# design.net
KiCad netlist of a schematic drawn in Altium Designer
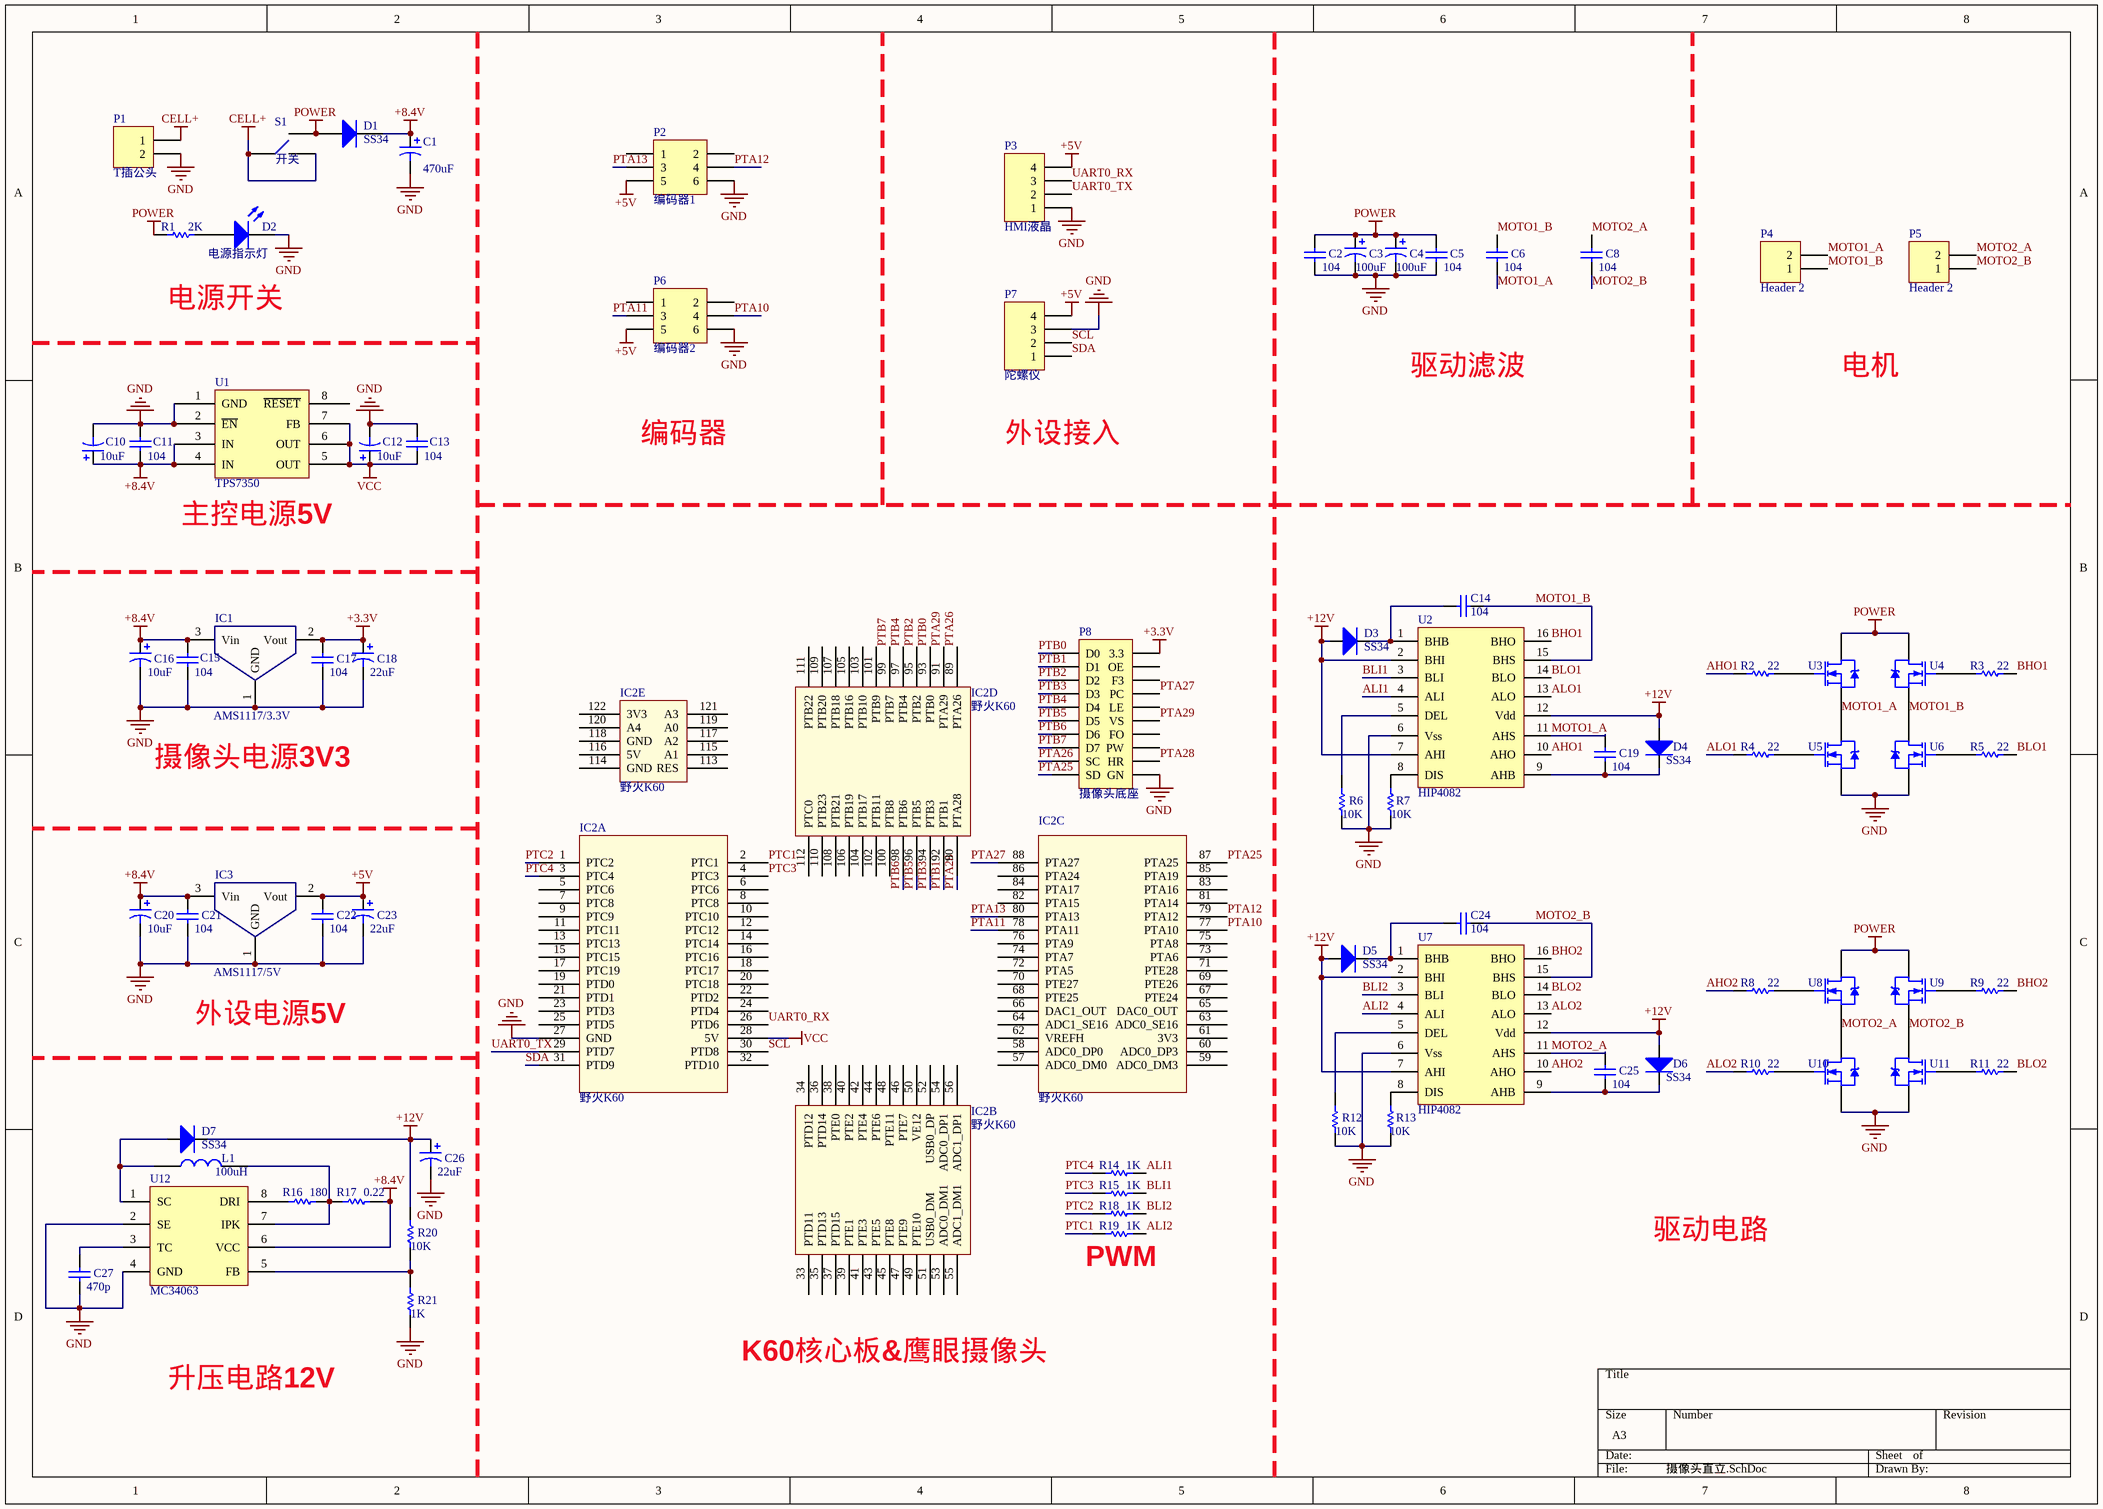
[diagram p0: 摄像头直立.SchDoc]

(export (version "E")
  (design (tool "Eeschema 10.0.6"))
  (components
    (comp (ref "C1")
      (value "470uF")
      (footprint "CAP_ELEC_250P680X1220_FLAT2")
      (description "Polarized Capacitor (Radial)")
      (fields (field (name "Comment") "Cap Pol1") (field (name "PUBLISHER") "Altium Limited"))
      (libsource (lib "Miscellaneous Devices") (part "Cap Pol1"))
    )
    (comp (ref "C2")
      (value "104")
      (footprint "CAP_0805")
      (description "Capacitor")
      (fields (field (name "Comment") "Cap") (field (name "PUBLISHER") "Altium Limited"))
      (libsource (lib "Miscellaneous Devices") (part "Cap"))
    )
    (comp (ref "C3")
      (value "100uF")
      (footprint "CAP_ELEC_250P680X1220_VERT")
      (description "Polarized Capacitor (Radial)")
      (fields (field (name "PUBLISHER") "Altium Limited"))
      (libsource (lib "Miscellaneous Devices") (part "Cap Pol1"))
    )
    (comp (ref "C4")
      (value "100uF")
      (footprint "CAP_ELEC_250P680X1220_VERT")
      (description "Polarized Capacitor (Radial)")
      (fields (field (name "PUBLISHER") "Altium Limited"))
      (libsource (lib "Miscellaneous Devices") (part "Cap Pol1"))
    )
    (comp (ref "C5")
      (value "104")
      (footprint "CAP_0805")
      (description "Capacitor")
      (fields (field (name "Comment") "Cap") (field (name "PUBLISHER") "Altium Limited"))
      (libsource (lib "Miscellaneous Devices") (part "Cap"))
    )
    (comp (ref "C6")
      (value "104")
      (footprint "CAP_0805")
      (description "Capacitor")
      (fields (field (name "Comment") "Cap") (field (name "PUBLISHER") "Altium Limited"))
      (libsource (lib "Miscellaneous Devices") (part "Cap"))
    )
    (comp (ref "C8")
      (value "104")
      (footprint "CAP_0805")
      (description "Capacitor")
      (fields (field (name "Comment") "Cap") (field (name "PUBLISHER") "Altium Limited"))
      (libsource (lib "Miscellaneous Devices") (part "Cap"))
    )
    (comp (ref "C10")
      (value "10uF")
      (footprint "CAP_0805")
      (description "Polarized Capacitor (Radial)")
      (fields (field (name "Comment") "Cap") (field (name "PUBLISHER") "Altium Limited"))
      (libsource (lib "Miscellaneous Devices") (part "Cap Pol1"))
    )
    (comp (ref "C11")
      (value "104")
      (footprint "CAP_0805")
      (description "Capacitor")
      (fields (field (name "Comment") "Cap") (field (name "PUBLISHER") "Altium Limited"))
      (libsource (lib "Miscellaneous Devices") (part "Cap"))
    )
    (comp (ref "C12")
      (value "10uF")
      (footprint "CAP_0805")
      (description "Polarized Capacitor (Radial)")
      (fields (field (name "Comment") "Cap") (field (name "PUBLISHER") "Altium Limited"))
      (libsource (lib "Miscellaneous Devices") (part "Cap Pol1"))
    )
    (comp (ref "C13")
      (value "104")
      (footprint "CAP_0805")
      (description "Capacitor")
      (fields (field (name "Comment") "Cap") (field (name "PUBLISHER") "Altium Limited"))
      (libsource (lib "Miscellaneous Devices") (part "Cap"))
    )
    (comp (ref "C14")
      (value "104")
      (footprint "CAP_0805")
      (description "Capacitor")
      (fields (field (name "Comment") "Cap") (field (name "PUBLISHER") "Altium Limited"))
      (libsource (lib "Miscellaneous Devices") (part "Cap"))
    )
    (comp (ref "C15")
      (value "104")
      (footprint "CAP_0805")
      (description "Capacitor")
      (fields (field (name "Comment") "Cap") (field (name "PUBLISHER") "Altium Limited"))
      (libsource (lib "Miscellaneous Devices") (part "Cap"))
    )
    (comp (ref "C16")
      (value "10uF")
      (footprint "CAP_0805")
      (description "Polarized Capacitor (Radial)")
      (fields (field (name "Comment") "Cap Pol1") (field (name "PUBLISHER") "Altium Limited"))
      (libsource (lib "Miscellaneous Devices") (part "Cap Pol1"))
    )
    (comp (ref "C17")
      (value "104")
      (footprint "CAP_0805")
      (description "Capacitor")
      (fields (field (name "Comment") "Cap") (field (name "PUBLISHER") "Altium Limited"))
      (libsource (lib "Miscellaneous Devices") (part "Cap"))
    )
    (comp (ref "C18")
      (value "22uF")
      (footprint "CAP_0805")
      (description "Polarized Capacitor (Radial)")
      (fields (field (name "Comment") "Cap Pol1") (field (name "PUBLISHER") "Altium Limited"))
      (libsource (lib "Miscellaneous Devices") (part "Cap Pol1"))
    )
    (comp (ref "C19")
      (value "104")
      (footprint "CAP_0805")
      (description "Capacitor")
      (fields (field (name "PUBLISHER") "Altium Limited"))
      (libsource (lib "Miscellaneous Devices") (part "Cap"))
    )
    (comp (ref "C20")
      (value "10uF")
      (footprint "CAP_0805")
      (description "Polarized Capacitor (Radial)")
      (fields (field (name "Comment") "Cap Pol1") (field (name "PUBLISHER") "Altium Limited"))
      (libsource (lib "Miscellaneous Devices") (part "Cap Pol1"))
    )
    (comp (ref "C21")
      (value "104")
      (footprint "CAP_0805")
      (description "Capacitor")
      (fields (field (name "Comment") "Cap") (field (name "PUBLISHER") "Altium Limited"))
      (libsource (lib "Miscellaneous Devices") (part "Cap"))
    )
    (comp (ref "C22")
      (value "104")
      (footprint "CAP_0805")
      (description "Capacitor")
      (fields (field (name "Comment") "Cap") (field (name "PUBLISHER") "Altium Limited"))
      (libsource (lib "Miscellaneous Devices") (part "Cap"))
    )
    (comp (ref "C23")
      (value "22uF")
      (footprint "CAP_0805")
      (description "Polarized Capacitor (Radial)")
      (fields (field (name "Comment") "Cap Pol1") (field (name "PUBLISHER") "Altium Limited"))
      (libsource (lib "Miscellaneous Devices") (part "Cap Pol1"))
    )
    (comp (ref "C24")
      (value "104")
      (footprint "CAP_0805")
      (description "Capacitor")
      (fields (field (name "Comment") "Cap") (field (name "PUBLISHER") "Altium Limited"))
      (libsource (lib "Miscellaneous Devices") (part "Cap"))
    )
    (comp (ref "C25")
      (value "104")
      (footprint "CAP_0805")
      (description "Capacitor")
      (fields (field (name "PUBLISHER") "Altium Limited"))
      (libsource (lib "Miscellaneous Devices") (part "Cap"))
    )
    (comp (ref "C26")
      (value "22uF")
      (footprint "CAP_0805")
      (description "Polarized Capacitor (Radial)")
      (fields (field (name "Comment") "Cap Pol1") (field (name "PUBLISHER") "Altium Limited"))
      (libsource (lib "Miscellaneous Devices") (part "Cap Pol1"))
    )
    (comp (ref "C27")
      (value "470p")
      (footprint "CAP_0805")
      (description "Capacitor")
      (fields (field (name "Comment") "Cap") (field (name "PUBLISHER") "Altium Limited"))
      (libsource (lib "Miscellaneous Devices") (part "Cap"))
    )
    (comp (ref "D1")
      (value "SS34")
      (footprint "SMA")
      (description "Default Diode")
      (fields (field (name "PUBLISHER") "Altium Limited"))
      (libsource (lib "Miscellaneous Devices") (part "Diode"))
    )
    (comp (ref "D2")
      (value "电源指示灯")
      (footprint "DIO_0805")
      (description "Typical INFRARED GaAs LED")
      (fields (field (name "PUBLISHER") "Altium Limited"))
      (libsource (lib "Miscellaneous Devices") (part "LED0"))
    )
    (comp (ref "D3") (value "SS34") (footprint "SMA") (libsource (lib "lr7843_new") (part "1n4007_2010")))
    (comp (ref "D4") (value "SS34") (footprint "SMA") (libsource (lib "lr7843_new") (part "1n4007_2010")))
    (comp (ref "D5") (value "SS34") (footprint "SMA") (libsource (lib "lr7843_new") (part "1n4007_2010")))
    (comp (ref "D6") (value "SS34") (footprint "SMA") (libsource (lib "lr7843_new") (part "1n4007_2010")))
    (comp (ref "D7") (value "SS34") (footprint "SMA") (libsource (lib "lr7843_new") (part "1n4007_2010")))
    (comp (ref "IC1")
      (value "AMS1117/3.3V")
      (footprint "SOT_223")
      (libsource (lib "Power_IC") (part "AMS1117"))
    )
    (comp (ref "IC2") (value "野火K60") (footprint "fireK60") (libsource (lib "Mcu_IC") (part "野火K60")))
    (comp (ref "IC3")
      (value "AMS1117/5V")
      (footprint "SOT_223")
      (libsource (lib "Power_IC") (part "AMS1117"))
    )
    (comp (ref "L1")
      (value "100uH")
      (footprint "L-5X4mm-S")
      (fields (field (name "Comment") "inductor"))
      (libsource (lib "lr7843_new") (part "inductor_CD43贴片"))
    )
    (comp (ref "P1")
      (value "T插公头")
      (footprint "T(G)")
      (description "Header, 2-Pin")
      (fields (field (name "PUBLISHER") "Altium Limited"))
      (libsource (lib "") (part "Header 2_1"))
    )
    (comp (ref "P2")
      (value "编码器1")
      (footprint "201R2X3")
      (description "Header, 3-Pin, Dual row")
      (fields (field (name "PUBLISHER") "Altium Limited"))
      (libsource (lib "Miscellaneous Connectors") (part "Header 3X2"))
    )
    (comp (ref "P3")
      (value "HMI液晶")
      (footprint "HDR1*4")
      (description "Header, 4-Pin")
      (fields (field (name "PUBLISHER") "Altium Limited"))
      (libsource (lib "Miscellaneous Connectors") (part "Header 4"))
    )
    (comp (ref "P4")
      (value "Header 2")
      (footprint "CON_5.08*2")
      (description "Header, 2-Pin")
      (fields (field (name "PUBLISHER") "Altium Limited"))
      (libsource (lib "Miscellaneous Connectors") (part "Header 2"))
    )
    (comp (ref "P5")
      (value "Header 2")
      (footprint "CON_5.08*2")
      (description "Header, 2-Pin")
      (fields (field (name "PUBLISHER") "Altium Limited"))
      (libsource (lib "Miscellaneous Connectors") (part "Header 2"))
    )
    (comp (ref "P6")
      (value "编码器2")
      (footprint "201R2X3")
      (description "Header, 3-Pin, Dual row")
      (fields (field (name "PUBLISHER") "Altium Limited"))
      (libsource (lib "Miscellaneous Connectors") (part "Header 3X2"))
    )
    (comp (ref "P7")
      (value "陀螺仪")
      (footprint "HDR1*4")
      (description "Header, 4-Pin")
      (fields (field (name "PUBLISHER") "Altium Limited"))
      (libsource (lib "Miscellaneous Connectors") (part "Header 4"))
    )
    (comp (ref "P8")
      (value "摄像头底座")
      (footprint "摄像头")
      (description "Header, 10-Pin, Dual row, Right Angle")
      (fields (field (name "PUBLISHER") "Altium Limited"))
      (libsource (lib "Miscellaneous Connectors") (part "Header 10X2H"))
    )
    (comp (ref "R1")
      (value "2K")
      (footprint "RES_0805")
      (description "Resistor")
      (fields (field (name "Comment") "Res1") (field (name "PUBLISHER") "Altium Limited"))
      (libsource (lib "Miscellaneous Devices") (part "Res1"))
    )
    (comp (ref "R2")
      (value "22")
      (footprint "RES_0805")
      (description "Resistor")
      (fields (field (name "Comment") "Res1") (field (name "PUBLISHER") "Altium Limited"))
      (libsource (lib "Miscellaneous Devices") (part "Res1"))
    )
    (comp (ref "R3")
      (value "22")
      (footprint "RES_0805")
      (description "Resistor")
      (fields (field (name "Comment") "Res1") (field (name "PUBLISHER") "Altium Limited"))
      (libsource (lib "Miscellaneous Devices") (part "Res1"))
    )
    (comp (ref "R4")
      (value "22")
      (footprint "RES_0805")
      (description "Resistor")
      (fields (field (name "Comment") "Res1") (field (name "PUBLISHER") "Altium Limited"))
      (libsource (lib "Miscellaneous Devices") (part "Res1"))
    )
    (comp (ref "R5")
      (value "22")
      (footprint "RES_0805")
      (description "Resistor")
      (fields (field (name "Comment") "Res1") (field (name "PUBLISHER") "Altium Limited"))
      (libsource (lib "Miscellaneous Devices") (part "Res1"))
    )
    (comp (ref "R6")
      (value "10K")
      (footprint "RES_0805")
      (description "Resistor")
      (fields (field (name "Comment") "Res1") (field (name "PUBLISHER") "Altium Limited"))
      (libsource (lib "Miscellaneous Devices") (part "Res1"))
    )
    (comp (ref "R7")
      (value "10K")
      (footprint "RES_0805")
      (description "Resistor")
      (fields (field (name "Comment") "Res1") (field (name "PUBLISHER") "Altium Limited"))
      (libsource (lib "Miscellaneous Devices") (part "Res1"))
    )
    (comp (ref "R8")
      (value "22")
      (footprint "RES_0805")
      (description "Resistor")
      (fields (field (name "Comment") "Res1") (field (name "PUBLISHER") "Altium Limited"))
      (libsource (lib "Miscellaneous Devices") (part "Res1"))
    )
    (comp (ref "R9")
      (value "22")
      (footprint "RES_0805")
      (description "Resistor")
      (fields (field (name "Comment") "Res1") (field (name "PUBLISHER") "Altium Limited"))
      (libsource (lib "Miscellaneous Devices") (part "Res1"))
    )
    (comp (ref "R10")
      (value "22")
      (footprint "RES_0805")
      (description "Resistor")
      (fields (field (name "Comment") "Res1") (field (name "PUBLISHER") "Altium Limited"))
      (libsource (lib "Miscellaneous Devices") (part "Res1"))
    )
    (comp (ref "R11")
      (value "22")
      (footprint "RES_0805")
      (description "Resistor")
      (fields (field (name "Comment") "Res1") (field (name "PUBLISHER") "Altium Limited"))
      (libsource (lib "Miscellaneous Devices") (part "Res1"))
    )
    (comp (ref "R12")
      (value "10K")
      (footprint "RES_0805")
      (description "Resistor")
      (fields (field (name "Comment") "Res1") (field (name "PUBLISHER") "Altium Limited"))
      (libsource (lib "Miscellaneous Devices") (part "Res1"))
    )
    (comp (ref "R13")
      (value "10K")
      (footprint "RES_0805")
      (description "Resistor")
      (fields (field (name "Comment") "Res1") (field (name "PUBLISHER") "Altium Limited"))
      (libsource (lib "Miscellaneous Devices") (part "Res1"))
    )
    (comp (ref "R14")
      (value "1K")
      (footprint "RES_0805")
      (description "Resistor")
      (fields (field (name "PUBLISHER") "Altium Limited"))
      (libsource (lib "Miscellaneous Devices") (part "Res1"))
    )
    (comp (ref "R15")
      (value "1K")
      (footprint "RES_0805")
      (description "Resistor")
      (fields (field (name "PUBLISHER") "Altium Limited"))
      (libsource (lib "Miscellaneous Devices") (part "Res1"))
    )
    (comp (ref "R16")
      (value "180")
      (footprint "RES_0805")
      (description "Resistor")
      (fields (field (name "PUBLISHER") "Altium Limited"))
      (libsource (lib "Miscellaneous Devices") (part "Res1"))
    )
    (comp (ref "R17")
      (value "0.22")
      (footprint "RES_1206")
      (description "Resistor")
      (fields (field (name "PUBLISHER") "Altium Limited"))
      (libsource (lib "Miscellaneous Devices") (part "Res1"))
    )
    (comp (ref "R18")
      (value "1K")
      (footprint "RES_0805")
      (description "Resistor")
      (fields (field (name "PUBLISHER") "Altium Limited"))
      (libsource (lib "Miscellaneous Devices") (part "Res1"))
    )
    (comp (ref "R19")
      (value "1K")
      (footprint "RES_0805")
      (description "Resistor")
      (fields (field (name "PUBLISHER") "Altium Limited"))
      (libsource (lib "Miscellaneous Devices") (part "Res1"))
    )
    (comp (ref "R20")
      (value "10K")
      (footprint "RES_0805")
      (description "Resistor")
      (fields (field (name "PUBLISHER") "Altium Limited"))
      (libsource (lib "Miscellaneous Devices") (part "Res1"))
    )
    (comp (ref "R21")
      (value "1K")
      (footprint "RES_0805")
      (description "Resistor")
      (fields (field (name "PUBLISHER") "Altium Limited"))
      (libsource (lib "Miscellaneous Devices") (part "Res1"))
    )
    (comp (ref "S1")
      (value "开关")
      (footprint "slide_switch")
      (libsource (lib "lr7843_new") (part "slide_switch"))
    )
    (comp (ref "U1") (value "TPS7350") (footprint "SOP_8") (libsource (lib "Power_IC") (part "TPS73XX")))
    (comp (ref "U2") (value "HIP4082") (footprint "HIP4082b") (libsource (lib "lr7843_new") (part "HIP4082")))
    (comp (ref "U3")
      (value "irlr7843")
      (footprint "TO-252AA")
      (libsource (lib "lr7843_new") (part "IRLR7843"))
    )
    (comp (ref "U4")
      (value "irlr7843")
      (footprint "TO-252AA")
      (libsource (lib "lr7843_new") (part "IRLR7843"))
    )
    (comp (ref "U5")
      (value "irlr7843")
      (footprint "TO-252AA")
      (libsource (lib "lr7843_new") (part "IRLR7843"))
    )
    (comp (ref "U6")
      (value "irlr7843")
      (footprint "TO-252AA")
      (libsource (lib "lr7843_new") (part "IRLR7843"))
    )
    (comp (ref "U7") (value "HIP4082") (footprint "HIP4082b") (libsource (lib "lr7843_new") (part "HIP4082")))
    (comp (ref "U8")
      (value "irlr7843")
      (footprint "TO-252AA")
      (libsource (lib "lr7843_new") (part "IRLR7843"))
    )
    (comp (ref "U9")
      (value "irlr7843")
      (footprint "TO-252AA")
      (libsource (lib "lr7843_new") (part "IRLR7843"))
    )
    (comp (ref "U10")
      (value "irlr7843")
      (footprint "TO-252AA")
      (libsource (lib "lr7843_new") (part "IRLR7843"))
    )
    (comp (ref "U11")
      (value "irlr7843")
      (footprint "TO-252AA")
      (libsource (lib "lr7843_new") (part "IRLR7843"))
    )
    (comp (ref "U12") (value "MC34063") (footprint "SOP_8") (libsource (lib "lr7843_new") (part "MC34063")))
  )
  (nets
    (net (code "1") (name "+3.3V") (class "Default")
      (node (ref "C17") (pin "2") (pinfunction "2_2") (pintype "passive"))
      (node (ref "C18") (pin "1") (pinfunction "1_1") (pintype "passive"))
      (node (ref "IC1") (pin "2") (pinfunction "Vout_2") (pintype "passive"))
      (node (ref "P8") (pin "2") (pinfunction "3.3_2") (pintype "passive"))
    )
    (net (code "2") (name "+5V") (class "Default")
      (node (ref "C22") (pin "2") (pinfunction "2_2") (pintype "passive"))
      (node (ref "C23") (pin "1") (pinfunction "1_1") (pintype "passive"))
      (node (ref "IC3") (pin "2") (pinfunction "Vout_2") (pintype "passive"))
      (node (ref "P2") (pin "5") (pinfunction "5_5") (pintype "passive"))
      (node (ref "P3") (pin "4") (pinfunction "4_4") (pintype "passive"))
      (node (ref "P6") (pin "5") (pinfunction "5_5") (pintype "passive"))
      (node (ref "P7") (pin "4") (pinfunction "4_4") (pintype "passive"))
    )
    (net (code "3") (name "+8.4V") (class "Default")
      (node (ref "C1") (pin "1") (pinfunction "1_1") (pintype "passive"))
      (node (ref "C10") (pin "1") (pinfunction "1_1") (pintype "passive"))
      (node (ref "C11") (pin "1") (pinfunction "1_1") (pintype "passive"))
      (node (ref "C15") (pin "2") (pinfunction "2_2") (pintype "passive"))
      (node (ref "C16") (pin "1") (pinfunction "1_1") (pintype "passive"))
      (node (ref "C20") (pin "1") (pinfunction "1_1") (pintype "passive"))
      (node (ref "C21") (pin "2") (pinfunction "2_2") (pintype "passive"))
      (node (ref "D1") (pin "2") (pinfunction "K_2") (pintype "passive"))
      (node (ref "IC1") (pin "3") (pinfunction "Vin_3") (pintype "passive"))
      (node (ref "IC3") (pin "3") (pinfunction "Vin_3") (pintype "passive"))
      (node (ref "R17") (pin "1") (pinfunction "1_1") (pintype "passive"))
      (node (ref "U1") (pin "3") (pinfunction "IN_3") (pintype "passive"))
      (node (ref "U1") (pin "4") (pinfunction "IN_4") (pintype "passive"))
      (node (ref "U12") (pin "6") (pinfunction "VCC_6") (pintype "passive"))
    )
    (net (code "4") (name "+12V") (class "Default")
      (node (ref "C26") (pin "1") (pinfunction "1_1") (pintype "passive"))
      (node (ref "D3") (pin "1") (pinfunction "A_1") (pintype "passive"))
      (node (ref "D4") (pin "1") (pinfunction "A_1") (pintype "passive"))
      (node (ref "D5") (pin "1") (pinfunction "A_1") (pintype "passive"))
      (node (ref "D6") (pin "1") (pinfunction "A_1") (pintype "passive"))
      (node (ref "D7") (pin "2") (pinfunction "K_2") (pintype "passive"))
      (node (ref "R20") (pin "2") (pinfunction "2_2") (pintype "passive"))
      (node (ref "U2") (pin "12") (pinfunction "Vdd_12") (pintype "passive"))
      (node (ref "U2") (pin "2") (pinfunction "BHI_2") (pintype "passive"))
      (node (ref "U2") (pin "7") (pinfunction "AHI_7") (pintype "passive"))
      (node (ref "U7") (pin "12") (pinfunction "Vdd_12") (pintype "passive"))
      (node (ref "U7") (pin "2") (pinfunction "BHI_2") (pintype "passive"))
      (node (ref "U7") (pin "7") (pinfunction "AHI_7") (pintype "passive"))
    )
    (net (code "5") (name "/AHO1") (class "Default")
      (node (ref "R2") (pin "2") (pinfunction "2_2") (pintype "passive"))
      (node (ref "U2") (pin "10") (pinfunction "AHO_10") (pintype "passive"))
    )
    (net (code "6") (name "/AHO2") (class "Default")
      (node (ref "R8") (pin "2") (pinfunction "2_2") (pintype "passive"))
      (node (ref "U7") (pin "10") (pinfunction "AHO_10") (pintype "passive"))
    )
    (net (code "7") (name "/ALI1") (class "Default")
      (node (ref "R14") (pin "1") (pinfunction "1_1") (pintype "passive"))
      (node (ref "U2") (pin "4") (pinfunction "ALI_4") (pintype "passive"))
    )
    (net (code "8") (name "/ALI2") (class "Default")
      (node (ref "R19") (pin "1") (pinfunction "1_1") (pintype "passive"))
      (node (ref "U7") (pin "4") (pinfunction "ALI_4") (pintype "passive"))
    )
    (net (code "9") (name "/ALO1") (class "Default")
      (node (ref "R4") (pin "2") (pinfunction "2_2") (pintype "passive"))
      (node (ref "U2") (pin "13") (pinfunction "ALO_13") (pintype "passive"))
    )
    (net (code "10") (name "/ALO2") (class "Default")
      (node (ref "R10") (pin "2") (pinfunction "2_2") (pintype "passive"))
      (node (ref "U7") (pin "13") (pinfunction "ALO_13") (pintype "passive"))
    )
    (net (code "11") (name "/BHO1") (class "Default")
      (node (ref "R3") (pin "1") (pinfunction "1_1") (pintype "passive"))
      (node (ref "U2") (pin "16") (pinfunction "BHO_16") (pintype "passive"))
    )
    (net (code "12") (name "/BHO2") (class "Default")
      (node (ref "R9") (pin "1") (pinfunction "1_1") (pintype "passive"))
      (node (ref "U7") (pin "16") (pinfunction "BHO_16") (pintype "passive"))
    )
    (net (code "13") (name "/BLI1") (class "Default")
      (node (ref "R15") (pin "1") (pinfunction "1_1") (pintype "passive"))
      (node (ref "U2") (pin "3") (pinfunction "BLI_3") (pintype "passive"))
    )
    (net (code "14") (name "/BLI2") (class "Default")
      (node (ref "R18") (pin "1") (pinfunction "1_1") (pintype "passive"))
      (node (ref "U7") (pin "3") (pinfunction "BLI_3") (pintype "passive"))
    )
    (net (code "15") (name "/BLO1") (class "Default")
      (node (ref "R5") (pin "1") (pinfunction "1_1") (pintype "passive"))
      (node (ref "U2") (pin "14") (pinfunction "BLO_14") (pintype "passive"))
    )
    (net (code "16") (name "/BLO2") (class "Default")
      (node (ref "R11") (pin "1") (pinfunction "1_1") (pintype "passive"))
      (node (ref "U7") (pin "14") (pinfunction "BLO_14") (pintype "passive"))
    )
    (net (code "17") (name "/MOTO1_A") (class "Default")
      (node (ref "C19") (pin "2") (pinfunction "2_2") (pintype "passive"))
      (node (ref "C6") (pin "2") (pinfunction "2_2") (pintype "passive"))
      (node (ref "P4") (pin "2") (pinfunction "2_2") (pintype "passive"))
      (node (ref "U2") (pin "11") (pinfunction "AHS_11") (pintype "passive"))
      (node (ref "U3") (pin "S") (pinfunction "S_S") (pintype "passive"))
      (node (ref "U5") (pin "D") (pinfunction "D_D") (pintype "passive"))
    )
    (net (code "18") (name "/MOTO1_B") (class "Default")
      (node (ref "C14") (pin "1") (pinfunction "1_1") (pintype "passive"))
      (node (ref "C6") (pin "1") (pinfunction "1_1") (pintype "passive"))
      (node (ref "P4") (pin "1") (pinfunction "1_1") (pintype "passive"))
      (node (ref "U2") (pin "15") (pinfunction "BHS_15") (pintype "passive"))
      (node (ref "U4") (pin "S") (pinfunction "S_S") (pintype "passive"))
      (node (ref "U6") (pin "D") (pinfunction "D_D") (pintype "passive"))
    )
    (net (code "19") (name "/MOTO2_A") (class "Default")
      (node (ref "C25") (pin "2") (pinfunction "2_2") (pintype "passive"))
      (node (ref "C8") (pin "1") (pinfunction "1_1") (pintype "passive"))
      (node (ref "P5") (pin "2") (pinfunction "2_2") (pintype "passive"))
      (node (ref "U10") (pin "D") (pinfunction "D_D") (pintype "passive"))
      (node (ref "U7") (pin "11") (pinfunction "AHS_11") (pintype "passive"))
      (node (ref "U8") (pin "S") (pinfunction "S_S") (pintype "passive"))
    )
    (net (code "20") (name "/MOTO2_B") (class "Default")
      (node (ref "C24") (pin "1") (pinfunction "1_1") (pintype "passive"))
      (node (ref "C8") (pin "2") (pinfunction "2_2") (pintype "passive"))
      (node (ref "P5") (pin "1") (pinfunction "1_1") (pintype "passive"))
      (node (ref "U11") (pin "D") (pinfunction "D_D") (pintype "passive"))
      (node (ref "U7") (pin "15") (pinfunction "BHS_15") (pintype "passive"))
      (node (ref "U9") (pin "S") (pinfunction "S_S") (pintype "passive"))
    )
    (net (code "21") (name "/PTA10") (class "Default")
      (node (ref "IC2") (pin "77") (pinfunction "PTA10_77") (pintype "passive"))
      (node (ref "P6") (pin "4") (pinfunction "4_4") (pintype "passive"))
    )
    (net (code "22") (name "/PTA11") (class "Default")
      (node (ref "IC2") (pin "78") (pinfunction "PTA11_78") (pintype "passive"))
      (node (ref "P6") (pin "3") (pinfunction "3_3") (pintype "passive"))
    )
    (net (code "23") (name "/PTA12") (class "Default")
      (node (ref "IC2") (pin "79") (pinfunction "PTA12_79") (pintype "passive"))
      (node (ref "P2") (pin "4") (pinfunction "4_4") (pintype "passive"))
    )
    (net (code "24") (name "/PTA13") (class "Default")
      (node (ref "IC2") (pin "80") (pinfunction "PTA13_80") (pintype "passive"))
      (node (ref "P2") (pin "3") (pinfunction "3_3") (pintype "passive"))
    )
    (net (code "25") (name "/PTA25") (class "Default")
      (node (ref "IC2") (pin "87") (pinfunction "PTA25_87") (pintype "passive"))
      (node (ref "P8") (pin "19") (pinfunction "SD_19") (pintype "passive"))
    )
    (net (code "26") (name "/PTA26") (class "Default")
      (node (ref "IC2") (pin "89") (pinfunction "PTA26_89") (pintype "passive"))
      (node (ref "P8") (pin "17") (pinfunction "SC_17") (pintype "passive"))
    )
    (net (code "27") (name "/PTA27") (class "Default")
      (node (ref "IC2") (pin "88") (pinfunction "PTA27_88") (pintype "passive"))
      (node (ref "P8") (pin "8") (pinfunction "PC_8") (pintype "passive"))
    )
    (net (code "28") (name "/PTA28") (class "Default")
      (node (ref "IC2") (pin "90") (pinfunction "PTA28_90") (pintype "passive"))
      (node (ref "P8") (pin "18") (pinfunction "HR_18") (pintype "passive"))
    )
    (net (code "29") (name "/PTA29") (class "Default")
      (node (ref "IC2") (pin "91") (pinfunction "PTA29_91") (pintype "passive"))
      (node (ref "P8") (pin "12") (pinfunction "VS_12") (pintype "passive"))
    )
    (net (code "30") (name "/PTB0") (class "Default")
      (node (ref "IC2") (pin "93") (pinfunction "PTB0_93") (pintype "passive"))
      (node (ref "P8") (pin "1") (pinfunction "D0_1") (pintype "passive"))
    )
    (net (code "31") (name "/PTB1") (class "Default")
      (node (ref "IC2") (pin "92") (pinfunction "PTB1_92") (pintype "passive"))
      (node (ref "P8") (pin "3") (pinfunction "D1_3") (pintype "passive"))
    )
    (net (code "32") (name "/PTB2") (class "Default")
      (node (ref "IC2") (pin "95") (pinfunction "PTB2_95") (pintype "passive"))
      (node (ref "P8") (pin "5") (pinfunction "D2_5") (pintype "passive"))
    )
    (net (code "33") (name "/PTB3") (class "Default")
      (node (ref "IC2") (pin "94") (pinfunction "PTB3_94") (pintype "passive"))
      (node (ref "P8") (pin "7") (pinfunction "D3_7") (pintype "passive"))
    )
    (net (code "34") (name "/PTB4") (class "Default")
      (node (ref "IC2") (pin "97") (pinfunction "PTB4_97") (pintype "passive"))
      (node (ref "P8") (pin "9") (pinfunction "D4_9") (pintype "passive"))
    )
    (net (code "35") (name "/PTB5") (class "Default")
      (node (ref "IC2") (pin "96") (pinfunction "PTB5_96") (pintype "passive"))
      (node (ref "P8") (pin "11") (pinfunction "D5_11") (pintype "passive"))
    )
    (net (code "36") (name "/PTB6") (class "Default")
      (node (ref "IC2") (pin "98") (pinfunction "PTB6_98") (pintype "passive"))
      (node (ref "P8") (pin "13") (pinfunction "D6_13") (pintype "passive"))
    )
    (net (code "37") (name "/PTB7") (class "Default")
      (node (ref "IC2") (pin "99") (pinfunction "PTB7_99") (pintype "passive"))
      (node (ref "P8") (pin "15") (pinfunction "D7_15") (pintype "passive"))
    )
    (net (code "38") (name "/PTC1") (class "Default")
      (node (ref "IC2") (pin "2") (pinfunction "PTC1_2") (pintype "passive"))
      (node (ref "R19") (pin "2") (pinfunction "2_2") (pintype "passive"))
    )
    (net (code "39") (name "/PTC2") (class "Default")
      (node (ref "IC2") (pin "1") (pinfunction "PTC2_1") (pintype "passive"))
      (node (ref "R18") (pin "2") (pinfunction "2_2") (pintype "passive"))
    )
    (net (code "40") (name "/PTC3") (class "Default")
      (node (ref "IC2") (pin "4") (pinfunction "PTC3_4") (pintype "passive"))
      (node (ref "R15") (pin "2") (pinfunction "2_2") (pintype "passive"))
    )
    (net (code "41") (name "/PTC4") (class "Default")
      (node (ref "IC2") (pin "3") (pinfunction "PTC4_3") (pintype "passive"))
      (node (ref "R14") (pin "2") (pinfunction "2_2") (pintype "passive"))
    )
    (net (code "42") (name "/SCL") (class "Default")
      (node (ref "IC2") (pin "30") (pinfunction "PTD8_30") (pintype "passive"))
      (node (ref "P7") (pin "2") (pinfunction "2_2") (pintype "passive"))
    )
    (net (code "43") (name "/SDA") (class "Default")
      (node (ref "IC2") (pin "31") (pinfunction "PTD9_31") (pintype "passive"))
      (node (ref "P7") (pin "1") (pinfunction "1_1") (pintype "passive"))
    )
    (net (code "44") (name "/UART0_RX") (class "Default")
      (node (ref "IC2") (pin "26") (pinfunction "PTD6_26") (pintype "passive"))
      (node (ref "P3") (pin "3") (pinfunction "3_3") (pintype "passive"))
    )
    (net (code "45") (name "/UART0_TX") (class "Default")
      (node (ref "IC2") (pin "29") (pinfunction "PTD7_29") (pintype "passive"))
      (node (ref "P3") (pin "2") (pinfunction "2_2") (pintype "passive"))
    )
    (net (code "46") (name "CELL+") (class "Default")
      (node (ref "P1") (pin "1") (pinfunction "1_1") (pintype "passive"))
      (node (ref "S1") (pin "1") (pinfunction "1_1") (pintype "passive"))
      (node (ref "S1") (pin "3") (pinfunction "3_3") (pintype "passive"))
    )
    (net (code "47") (name "GND") (class "Default")
      (node (ref "C1") (pin "2") (pinfunction "2_2") (pintype "passive"))
      (node (ref "C10") (pin "2") (pinfunction "2_2") (pintype "passive"))
      (node (ref "C11") (pin "2") (pinfunction "2_2") (pintype "passive"))
      (node (ref "C12") (pin "2") (pinfunction "2_2") (pintype "passive"))
      (node (ref "C13") (pin "1") (pinfunction "1_1") (pintype "passive"))
      (node (ref "C15") (pin "1") (pinfunction "1_1") (pintype "passive"))
      (node (ref "C16") (pin "2") (pinfunction "2_2") (pintype "passive"))
      (node (ref "C17") (pin "1") (pinfunction "1_1") (pintype "passive"))
      (node (ref "C18") (pin "2") (pinfunction "2_2") (pintype "passive"))
      (node (ref "C2") (pin "2") (pinfunction "2_2") (pintype "passive"))
      (node (ref "C20") (pin "2") (pinfunction "2_2") (pintype "passive"))
      (node (ref "C21") (pin "1") (pinfunction "1_1") (pintype "passive"))
      (node (ref "C22") (pin "1") (pinfunction "1_1") (pintype "passive"))
      (node (ref "C23") (pin "2") (pinfunction "2_2") (pintype "passive"))
      (node (ref "C26") (pin "2") (pinfunction "2_2") (pintype "passive"))
      (node (ref "C27") (pin "1") (pinfunction "1_1") (pintype "passive"))
      (node (ref "C3") (pin "2") (pinfunction "2_2") (pintype "passive"))
      (node (ref "C4") (pin "2") (pinfunction "2_2") (pintype "passive"))
      (node (ref "C5") (pin "2") (pinfunction "2_2") (pintype "passive"))
      (node (ref "D2") (pin "2") (pinfunction "K_2") (pintype "passive"))
      (node (ref "IC1") (pin "1") (pinfunction "GND_1") (pintype "passive"))
      (node (ref "IC2") (pin "27") (pinfunction "GND_27") (pintype "passive"))
      (node (ref "IC3") (pin "1") (pinfunction "GND_1") (pintype "passive"))
      (node (ref "P1") (pin "2") (pinfunction "2_2") (pintype "passive"))
      (node (ref "P2") (pin "6") (pinfunction "6_6") (pintype "passive"))
      (node (ref "P3") (pin "1") (pinfunction "1_1") (pintype "passive"))
      (node (ref "P6") (pin "6") (pinfunction "6_6") (pintype "passive"))
      (node (ref "P7") (pin "3") (pinfunction "3_3") (pintype "passive"))
      (node (ref "P8") (pin "20") (pinfunction "GN_20") (pintype "passive"))
      (node (ref "R12") (pin "1") (pinfunction "1_1") (pintype "passive"))
      (node (ref "R13") (pin "1") (pinfunction "1_1") (pintype "passive"))
      (node (ref "R21") (pin "1") (pinfunction "1_1") (pintype "passive"))
      (node (ref "R6") (pin "1") (pinfunction "1_1") (pintype "passive"))
      (node (ref "R7") (pin "1") (pinfunction "1_1") (pintype "passive"))
      (node (ref "U1") (pin "1") (pinfunction "GND_1") (pintype "passive"))
      (node (ref "U1") (pin "2") (pinfunction "~{EN}_2") (pintype "passive"))
      (node (ref "U10") (pin "S") (pinfunction "S_S") (pintype "passive"))
      (node (ref "U11") (pin "S") (pinfunction "S_S") (pintype "passive"))
      (node (ref "U12") (pin "2") (pinfunction "SE_2") (pintype "passive"))
      (node (ref "U12") (pin "4") (pinfunction "GND_4") (pintype "passive"))
      (node (ref "U2") (pin "6") (pinfunction "Vss_6") (pintype "passive"))
      (node (ref "U5") (pin "S") (pinfunction "S_S") (pintype "passive"))
      (node (ref "U6") (pin "S") (pinfunction "S_S") (pintype "passive"))
      (node (ref "U7") (pin "6") (pinfunction "Vss_6") (pintype "passive"))
    )
    (net (code "48") (name "Net-(D2-A)") (class "Default")
      (node (ref "D2") (pin "1") (pinfunction "A_1") (pintype "passive"))
      (node (ref "R1") (pin "1") (pinfunction "1_1") (pintype "passive"))
    )
    (net (code "49") (name "Net-(D3-K)") (class "Default")
      (node (ref "C14") (pin "2") (pinfunction "2_2") (pintype "passive"))
      (node (ref "D3") (pin "2") (pinfunction "K_2") (pintype "passive"))
      (node (ref "U2") (pin "1") (pinfunction "BHB_1") (pintype "passive"))
    )
    (net (code "50") (name "Net-(D4-K)") (class "Default")
      (node (ref "C19") (pin "1") (pinfunction "1_1") (pintype "passive"))
      (node (ref "D4") (pin "2") (pinfunction "K_2") (pintype "passive"))
      (node (ref "U2") (pin "9") (pinfunction "AHB_9") (pintype "passive"))
    )
    (net (code "51") (name "Net-(D5-K)") (class "Default")
      (node (ref "C24") (pin "2") (pinfunction "2_2") (pintype "passive"))
      (node (ref "D5") (pin "2") (pinfunction "K_2") (pintype "passive"))
      (node (ref "U7") (pin "1") (pinfunction "BHB_1") (pintype "passive"))
    )
    (net (code "52") (name "Net-(D6-K)") (class "Default")
      (node (ref "C25") (pin "1") (pinfunction "1_1") (pintype "passive"))
      (node (ref "D6") (pin "2") (pinfunction "K_2") (pintype "passive"))
      (node (ref "U7") (pin "9") (pinfunction "AHB_9") (pintype "passive"))
    )
    (net (code "53") (name "Net-(D7-A)") (class "Default")
      (node (ref "D7") (pin "1") (pinfunction "A_1") (pintype "passive"))
      (node (ref "L1") (pin "1") (pinfunction "1_1") (pintype "passive"))
      (node (ref "U12") (pin "1") (pinfunction "SC_1") (pintype "passive"))
    )
    (net (code "54") (name "Net-(R2-Pad1)") (class "Default")
      (node (ref "R2") (pin "1") (pinfunction "1_1") (pintype "passive"))
      (node (ref "U3") (pin "G") (pinfunction "G_G") (pintype "passive"))
    )
    (net (code "55") (name "Net-(R3-Pad2)") (class "Default")
      (node (ref "R3") (pin "2") (pinfunction "2_2") (pintype "passive"))
      (node (ref "U4") (pin "G") (pinfunction "G_G") (pintype "passive"))
    )
    (net (code "56") (name "Net-(R4-Pad1)") (class "Default")
      (node (ref "R4") (pin "1") (pinfunction "1_1") (pintype "passive"))
      (node (ref "U5") (pin "G") (pinfunction "G_G") (pintype "passive"))
    )
    (net (code "57") (name "Net-(R5-Pad2)") (class "Default")
      (node (ref "R5") (pin "2") (pinfunction "2_2") (pintype "passive"))
      (node (ref "U6") (pin "G") (pinfunction "G_G") (pintype "passive"))
    )
    (net (code "58") (name "Net-(R8-Pad1)") (class "Default")
      (node (ref "R8") (pin "1") (pinfunction "1_1") (pintype "passive"))
      (node (ref "U8") (pin "G") (pinfunction "G_G") (pintype "passive"))
    )
    (net (code "59") (name "Net-(R9-Pad2)") (class "Default")
      (node (ref "R9") (pin "2") (pinfunction "2_2") (pintype "passive"))
      (node (ref "U9") (pin "G") (pinfunction "G_G") (pintype "passive"))
    )
    (net (code "60") (name "Net-(R10-Pad1)") (class "Default")
      (node (ref "R10") (pin "1") (pinfunction "1_1") (pintype "passive"))
      (node (ref "U10") (pin "G") (pinfunction "G_G") (pintype "passive"))
    )
    (net (code "61") (name "Net-(R11-Pad2)") (class "Default")
      (node (ref "R11") (pin "2") (pinfunction "2_2") (pintype "passive"))
      (node (ref "U11") (pin "G") (pinfunction "G_G") (pintype "passive"))
    )
    (net (code "62") (name "Net-(U2-DEL)") (class "Default")
      (node (ref "R6") (pin "2") (pinfunction "2_2") (pintype "passive"))
      (node (ref "U2") (pin "5") (pinfunction "DEL_5") (pintype "passive"))
    )
    (net (code "63") (name "Net-(U2-DIS)") (class "Default")
      (node (ref "R7") (pin "2") (pinfunction "2_2") (pintype "passive"))
      (node (ref "U2") (pin "8") (pinfunction "DIS_8") (pintype "passive"))
    )
    (net (code "64") (name "Net-(U7-DEL)") (class "Default")
      (node (ref "R12") (pin "2") (pinfunction "2_2") (pintype "passive"))
      (node (ref "U7") (pin "5") (pinfunction "DEL_5") (pintype "passive"))
    )
    (net (code "65") (name "Net-(U7-DIS)") (class "Default")
      (node (ref "R13") (pin "2") (pinfunction "2_2") (pintype "passive"))
      (node (ref "U7") (pin "8") (pinfunction "DIS_8") (pintype "passive"))
    )
    (net (code "66") (name "Net-(U12-DRI)") (class "Default")
      (node (ref "R16") (pin "2") (pinfunction "2_2") (pintype "passive"))
      (node (ref "U12") (pin "8") (pinfunction "DRI_8") (pintype "passive"))
    )
    (net (code "67") (name "Net-(U12-FB)") (class "Default")
      (node (ref "R20") (pin "1") (pinfunction "1_1") (pintype "passive"))
      (node (ref "R21") (pin "2") (pinfunction "2_2") (pintype "passive"))
      (node (ref "U12") (pin "5") (pinfunction "FB_5") (pintype "passive"))
    )
    (net (code "68") (name "Net-(U12-IPK)") (class "Default")
      (node (ref "L1") (pin "2") (pinfunction "2_2") (pintype "passive"))
      (node (ref "R16") (pin "1") (pinfunction "1_1") (pintype "passive"))
      (node (ref "R17") (pin "2") (pinfunction "2_2") (pintype "passive"))
      (node (ref "U12") (pin "7") (pinfunction "IPK_7") (pintype "passive"))
    )
    (net (code "69") (name "Net-(U12-TC)") (class "Default")
      (node (ref "C27") (pin "2") (pinfunction "2_2") (pintype "passive"))
      (node (ref "U12") (pin "3") (pinfunction "TC_3") (pintype "passive"))
    )
    (net (code "70") (name "POWER") (class "Default")
      (node (ref "C2") (pin "1") (pinfunction "1_1") (pintype "passive"))
      (node (ref "C3") (pin "1") (pinfunction "1_1") (pintype "passive"))
      (node (ref "C4") (pin "1") (pinfunction "1_1") (pintype "passive"))
      (node (ref "C5") (pin "1") (pinfunction "1_1") (pintype "passive"))
      (node (ref "D1") (pin "1") (pinfunction "A_1") (pintype "passive"))
      (node (ref "R1") (pin "2") (pinfunction "2_2") (pintype "passive"))
      (node (ref "S1") (pin "2") (pinfunction "2_2") (pintype "passive"))
      (node (ref "U3") (pin "D") (pinfunction "D_D") (pintype "passive"))
      (node (ref "U4") (pin "D") (pinfunction "D_D") (pintype "passive"))
      (node (ref "U8") (pin "D") (pinfunction "D_D") (pintype "passive"))
      (node (ref "U9") (pin "D") (pinfunction "D_D") (pintype "passive"))
    )
    (net (code "71") (name "VCC") (class "Default")
      (node (ref "C12") (pin "1") (pinfunction "1_1") (pintype "passive"))
      (node (ref "C13") (pin "2") (pinfunction "2_2") (pintype "passive"))
      (node (ref "IC2") (pin "28") (pinfunction "5V_28") (pintype "passive"))
      (node (ref "U1") (pin "5") (pinfunction "OUT_5") (pintype "passive"))
      (node (ref "U1") (pin "6") (pinfunction "OUT_6") (pintype "passive"))
      (node (ref "U1") (pin "7") (pinfunction "FB_7") (pintype "passive"))
    )
    (net (code "72") (name "unconnected-(IC2A-PTC6-Pad5)") (class "Default")
      (node (ref "IC2") (pin "5") (pinfunction "PTC6_5") (pintype "passive"))
    )
    (net (code "73") (name "unconnected-(IC2A-PTC6-Pad6)") (class "Default")
      (node (ref "IC2") (pin "6") (pinfunction "PTC6_6") (pintype "passive"))
    )
    (net (code "74") (name "unconnected-(IC2A-PTC8-Pad7)") (class "Default")
      (node (ref "IC2") (pin "7") (pinfunction "PTC8_7") (pintype "passive"))
    )
    (net (code "75") (name "unconnected-(IC2A-PTC8-Pad8)") (class "Default")
      (node (ref "IC2") (pin "8") (pinfunction "PTC8_8") (pintype "passive"))
    )
    (net (code "76") (name "unconnected-(IC2A-PTC9-Pad9)") (class "Default")
      (node (ref "IC2") (pin "9") (pinfunction "PTC9_9") (pintype "passive"))
    )
    (net (code "77") (name "unconnected-(IC2A-PTC10-Pad10)") (class "Default")
      (node (ref "IC2") (pin "10") (pinfunction "PTC10_10") (pintype "passive"))
    )
    (net (code "78") (name "unconnected-(IC2A-PTC11-Pad11)") (class "Default")
      (node (ref "IC2") (pin "11") (pinfunction "PTC11_11") (pintype "passive"))
    )
    (net (code "79") (name "unconnected-(IC2A-PTC12-Pad12)") (class "Default")
      (node (ref "IC2") (pin "12") (pinfunction "PTC12_12") (pintype "passive"))
    )
    (net (code "80") (name "unconnected-(IC2A-PTC13-Pad13)") (class "Default")
      (node (ref "IC2") (pin "13") (pinfunction "PTC13_13") (pintype "passive"))
    )
    (net (code "81") (name "unconnected-(IC2A-PTC14-Pad14)") (class "Default")
      (node (ref "IC2") (pin "14") (pinfunction "PTC14_14") (pintype "passive"))
    )
    (net (code "82") (name "unconnected-(IC2A-PTC15-Pad15)") (class "Default")
      (node (ref "IC2") (pin "15") (pinfunction "PTC15_15") (pintype "passive"))
    )
    (net (code "83") (name "unconnected-(IC2A-PTC16-Pad16)") (class "Default")
      (node (ref "IC2") (pin "16") (pinfunction "PTC16_16") (pintype "passive"))
    )
    (net (code "84") (name "unconnected-(IC2A-PTC17-Pad18)") (class "Default")
      (node (ref "IC2") (pin "18") (pinfunction "PTC17_18") (pintype "passive"))
    )
    (net (code "85") (name "unconnected-(IC2A-PTC18-Pad20)") (class "Default")
      (node (ref "IC2") (pin "20") (pinfunction "PTC18_20") (pintype "passive"))
    )
    (net (code "86") (name "unconnected-(IC2A-PTC19-Pad17)") (class "Default")
      (node (ref "IC2") (pin "17") (pinfunction "PTC19_17") (pintype "passive"))
    )
    (net (code "87") (name "unconnected-(IC2A-PTD0-Pad19)") (class "Default")
      (node (ref "IC2") (pin "19") (pinfunction "PTD0_19") (pintype "passive"))
    )
    (net (code "88") (name "unconnected-(IC2A-PTD1-Pad21)") (class "Default")
      (node (ref "IC2") (pin "21") (pinfunction "PTD1_21") (pintype "passive"))
    )
    (net (code "89") (name "unconnected-(IC2A-PTD2-Pad22)") (class "Default")
      (node (ref "IC2") (pin "22") (pinfunction "PTD2_22") (pintype "passive"))
    )
    (net (code "90") (name "unconnected-(IC2A-PTD3-Pad23)") (class "Default")
      (node (ref "IC2") (pin "23") (pinfunction "PTD3_23") (pintype "passive"))
    )
    (net (code "91") (name "unconnected-(IC2A-PTD4-Pad24)") (class "Default")
      (node (ref "IC2") (pin "24") (pinfunction "PTD4_24") (pintype "passive"))
    )
    (net (code "92") (name "unconnected-(IC2A-PTD5-Pad25)") (class "Default")
      (node (ref "IC2") (pin "25") (pinfunction "PTD5_25") (pintype "passive"))
    )
    (net (code "93") (name "unconnected-(IC2A-PTD10-Pad32)") (class "Default")
      (node (ref "IC2") (pin "32") (pinfunction "PTD10_32") (pintype "passive"))
    )
    (net (code "94") (name "unconnected-(IC2B-ADC0_DM1-Pad53)") (class "Default")
      (node (ref "IC2") (pin "53") (pinfunction "ADC0_DM1_53") (pintype "passive"))
    )
    (net (code "95") (name "unconnected-(IC2B-ADC0_DP1-Pad54)") (class "Default")
      (node (ref "IC2") (pin "54") (pinfunction "ADC0_DP1_54") (pintype "passive"))
    )
    (net (code "96") (name "unconnected-(IC2B-ADC1_DM1-Pad55)") (class "Default")
      (node (ref "IC2") (pin "55") (pinfunction "ADC1_DM1_55") (pintype "passive"))
    )
    (net (code "97") (name "unconnected-(IC2B-ADC1_DP1-Pad56)") (class "Default")
      (node (ref "IC2") (pin "56") (pinfunction "ADC1_DP1_56") (pintype "passive"))
    )
    (net (code "98") (name "unconnected-(IC2B-PTD11-Pad33)") (class "Default")
      (node (ref "IC2") (pin "33") (pinfunction "PTD11_33") (pintype "passive"))
    )
    (net (code "99") (name "unconnected-(IC2B-PTD12-Pad34)") (class "Default")
      (node (ref "IC2") (pin "34") (pinfunction "PTD12_34") (pintype "passive"))
    )
    (net (code "100") (name "unconnected-(IC2B-PTD13-Pad35)") (class "Default")
      (node (ref "IC2") (pin "35") (pinfunction "PTD13_35") (pintype "passive"))
    )
    (net (code "101") (name "unconnected-(IC2B-PTD14-Pad36)") (class "Default")
      (node (ref "IC2") (pin "36") (pinfunction "PTD14_36") (pintype "passive"))
    )
    (net (code "102") (name "unconnected-(IC2B-PTD15-Pad37)") (class "Default")
      (node (ref "IC2") (pin "37") (pinfunction "PTD15_37") (pintype "passive"))
    )
    (net (code "103") (name "unconnected-(IC2B-PTE0-Pad38)") (class "Default")
      (node (ref "IC2") (pin "38") (pinfunction "PTE0_38") (pintype "passive"))
    )
    (net (code "104") (name "unconnected-(IC2B-PTE1-Pad39)") (class "Default")
      (node (ref "IC2") (pin "39") (pinfunction "PTE1_39") (pintype "passive"))
    )
    (net (code "105") (name "unconnected-(IC2B-PTE2-Pad40)") (class "Default")
      (node (ref "IC2") (pin "40") (pinfunction "PTE2_40") (pintype "passive"))
    )
    (net (code "106") (name "unconnected-(IC2B-PTE3-Pad41)") (class "Default")
      (node (ref "IC2") (pin "41") (pinfunction "PTE3_41") (pintype "passive"))
    )
    (net (code "107") (name "unconnected-(IC2B-PTE4-Pad42)") (class "Default")
      (node (ref "IC2") (pin "42") (pinfunction "PTE4_42") (pintype "passive"))
    )
    (net (code "108") (name "unconnected-(IC2B-PTE5-Pad43)") (class "Default")
      (node (ref "IC2") (pin "43") (pinfunction "PTE5_43") (pintype "passive"))
    )
    (net (code "109") (name "unconnected-(IC2B-PTE6-Pad44)") (class "Default")
      (node (ref "IC2") (pin "44") (pinfunction "PTE6_44") (pintype "passive"))
    )
    (net (code "110") (name "unconnected-(IC2B-PTE7-Pad46)") (class "Default")
      (node (ref "IC2") (pin "46") (pinfunction "PTE7_46") (pintype "passive"))
    )
    (net (code "111") (name "unconnected-(IC2B-PTE8-Pad45)") (class "Default")
      (node (ref "IC2") (pin "45") (pinfunction "PTE8_45") (pintype "passive"))
    )
    (net (code "112") (name "unconnected-(IC2B-PTE9-Pad47)") (class "Default")
      (node (ref "IC2") (pin "47") (pinfunction "PTE9_47") (pintype "passive"))
    )
    (net (code "113") (name "unconnected-(IC2B-PTE10-Pad49)") (class "Default")
      (node (ref "IC2") (pin "49") (pinfunction "PTE10_49") (pintype "passive"))
    )
    (net (code "114") (name "unconnected-(IC2B-PTE11-Pad48)") (class "Default")
      (node (ref "IC2") (pin "48") (pinfunction "PTE11_48") (pintype "passive"))
    )
    (net (code "115") (name "unconnected-(IC2B-USB0_DM-Pad51)") (class "Default")
      (node (ref "IC2") (pin "51") (pinfunction "USB0_DM_51") (pintype "passive"))
    )
    (net (code "116") (name "unconnected-(IC2B-USB0_DP-Pad52)") (class "Default")
      (node (ref "IC2") (pin "52") (pinfunction "USB0_DP_52") (pintype "passive"))
    )
    (net (code "117") (name "unconnected-(IC2B-VE12-Pad50)") (class "Default")
      (node (ref "IC2") (pin "50") (pinfunction "VE12_50") (pintype "passive"))
    )
    (net (code "118") (name "unconnected-(IC2C-3V3-Pad61)") (class "Default")
      (node (ref "IC2") (pin "61") (pinfunction "3V3_61") (pintype "passive"))
    )
    (net (code "119") (name "unconnected-(IC2C-ADC0_DM0-Pad57)") (class "Default")
      (node (ref "IC2") (pin "57") (pinfunction "ADC0_DM0_57") (pintype "passive"))
    )
    (net (code "120") (name "unconnected-(IC2C-ADC0_DM3-Pad59)") (class "Default")
      (node (ref "IC2") (pin "59") (pinfunction "ADC0_DM3_59") (pintype "passive"))
    )
    (net (code "121") (name "unconnected-(IC2C-ADC0_DP0-Pad58)") (class "Default")
      (node (ref "IC2") (pin "58") (pinfunction "ADC0_DP0_58") (pintype "passive"))
    )
    (net (code "122") (name "unconnected-(IC2C-ADC0_DP3-Pad60)") (class "Default")
      (node (ref "IC2") (pin "60") (pinfunction "ADC0_DP3_60") (pintype "passive"))
    )
    (net (code "123") (name "unconnected-(IC2C-ADC0_SE16-Pad63)") (class "Default")
      (node (ref "IC2") (pin "63") (pinfunction "ADC0_SE16_63") (pintype "passive"))
    )
    (net (code "124") (name "unconnected-(IC2C-ADC1_SE16-Pad64)") (class "Default")
      (node (ref "IC2") (pin "64") (pinfunction "ADC1_SE16_64") (pintype "passive"))
    )
    (net (code "125") (name "unconnected-(IC2C-DAC0_OUT-Pad65)") (class "Default")
      (node (ref "IC2") (pin "65") (pinfunction "DAC0_OUT_65") (pintype "passive"))
    )
    (net (code "126") (name "unconnected-(IC2C-DAC1_OUT-Pad66)") (class "Default")
      (node (ref "IC2") (pin "66") (pinfunction "DAC1_OUT_66") (pintype "passive"))
    )
    (net (code "127") (name "unconnected-(IC2C-PTA5-Pad72)") (class "Default")
      (node (ref "IC2") (pin "72") (pinfunction "PTA5_72") (pintype "passive"))
    )
    (net (code "128") (name "unconnected-(IC2C-PTA6-Pad73)") (class "Default")
      (node (ref "IC2") (pin "73") (pinfunction "PTA6_73") (pintype "passive"))
    )
    (net (code "129") (name "unconnected-(IC2C-PTA7-Pad74)") (class "Default")
      (node (ref "IC2") (pin "74") (pinfunction "PTA7_74") (pintype "passive"))
    )
    (net (code "130") (name "unconnected-(IC2C-PTA8-Pad75)") (class "Default")
      (node (ref "IC2") (pin "75") (pinfunction "PTA8_75") (pintype "passive"))
    )
    (net (code "131") (name "unconnected-(IC2C-PTA9-Pad76)") (class "Default")
      (node (ref "IC2") (pin "76") (pinfunction "PTA9_76") (pintype "passive"))
    )
    (net (code "132") (name "unconnected-(IC2C-PTA14-Pad81)") (class "Default")
      (node (ref "IC2") (pin "81") (pinfunction "PTA14_81") (pintype "passive"))
    )
    (net (code "133") (name "unconnected-(IC2C-PTA15-Pad82)") (class "Default")
      (node (ref "IC2") (pin "82") (pinfunction "PTA15_82") (pintype "passive"))
    )
    (net (code "134") (name "unconnected-(IC2C-PTA16-Pad83)") (class "Default")
      (node (ref "IC2") (pin "83") (pinfunction "PTA16_83") (pintype "passive"))
    )
    (net (code "135") (name "unconnected-(IC2C-PTA17-Pad84)") (class "Default")
      (node (ref "IC2") (pin "84") (pinfunction "PTA17_84") (pintype "passive"))
    )
    (net (code "136") (name "unconnected-(IC2C-PTA19-Pad85)") (class "Default")
      (node (ref "IC2") (pin "85") (pinfunction "PTA19_85") (pintype "passive"))
    )
    (net (code "137") (name "unconnected-(IC2C-PTA24-Pad86)") (class "Default")
      (node (ref "IC2") (pin "86") (pinfunction "PTA24_86") (pintype "passive"))
    )
    (net (code "138") (name "unconnected-(IC2C-PTE24-Pad67)") (class "Default")
      (node (ref "IC2") (pin "67") (pinfunction "PTE24_67") (pintype "passive"))
    )
    (net (code "139") (name "unconnected-(IC2C-PTE25-Pad68)") (class "Default")
      (node (ref "IC2") (pin "68") (pinfunction "PTE25_68") (pintype "passive"))
    )
    (net (code "140") (name "unconnected-(IC2C-PTE26-Pad69)") (class "Default")
      (node (ref "IC2") (pin "69") (pinfunction "PTE26_69") (pintype "passive"))
    )
    (net (code "141") (name "unconnected-(IC2C-PTE27-Pad70)") (class "Default")
      (node (ref "IC2") (pin "70") (pinfunction "PTE27_70") (pintype "passive"))
    )
    (net (code "142") (name "unconnected-(IC2C-PTE28-Pad71)") (class "Default")
      (node (ref "IC2") (pin "71") (pinfunction "PTE28_71") (pintype "passive"))
    )
    (net (code "143") (name "unconnected-(IC2C-VREFH-Pad62)") (class "Default")
      (node (ref "IC2") (pin "62") (pinfunction "VREFH_62") (pintype "passive"))
    )
    (net (code "144") (name "unconnected-(IC2D-PTB8-Pad100)") (class "Default")
      (node (ref "IC2") (pin "100") (pinfunction "PTB8_100") (pintype "passive"))
    )
    (net (code "145") (name "unconnected-(IC2D-PTB9-Pad101)") (class "Default")
      (node (ref "IC2") (pin "101") (pinfunction "PTB9_101") (pintype "passive"))
    )
    (net (code "146") (name "unconnected-(IC2D-PTB10-Pad103)") (class "Default")
      (node (ref "IC2") (pin "103") (pinfunction "PTB10_103") (pintype "passive"))
    )
    (net (code "147") (name "unconnected-(IC2D-PTB11-Pad102)") (class "Default")
      (node (ref "IC2") (pin "102") (pinfunction "PTB11_102") (pintype "passive"))
    )
    (net (code "148") (name "unconnected-(IC2D-PTB16-Pad105)") (class "Default")
      (node (ref "IC2") (pin "105") (pinfunction "PTB16_105") (pintype "passive"))
    )
    (net (code "149") (name "unconnected-(IC2D-PTB17-Pad104)") (class "Default")
      (node (ref "IC2") (pin "104") (pinfunction "PTB17_104") (pintype "passive"))
    )
    (net (code "150") (name "unconnected-(IC2D-PTB18-Pad107)") (class "Default")
      (node (ref "IC2") (pin "107") (pinfunction "PTB18_107") (pintype "passive"))
    )
    (net (code "151") (name "unconnected-(IC2D-PTB19-Pad106)") (class "Default")
      (node (ref "IC2") (pin "106") (pinfunction "PTB19_106") (pintype "passive"))
    )
    (net (code "152") (name "unconnected-(IC2D-PTB20-Pad109)") (class "Default")
      (node (ref "IC2") (pin "109") (pinfunction "PTB20_109") (pintype "passive"))
    )
    (net (code "153") (name "unconnected-(IC2D-PTB21-Pad108)") (class "Default")
      (node (ref "IC2") (pin "108") (pinfunction "PTB21_108") (pintype "passive"))
    )
    (net (code "154") (name "unconnected-(IC2D-PTB22-Pad111)") (class "Default")
      (node (ref "IC2") (pin "111") (pinfunction "PTB22_111") (pintype "passive"))
    )
    (net (code "155") (name "unconnected-(IC2D-PTB23-Pad110)") (class "Default")
      (node (ref "IC2") (pin "110") (pinfunction "PTB23_110") (pintype "passive"))
    )
    (net (code "156") (name "unconnected-(IC2D-PTC0-Pad112)") (class "Default")
      (node (ref "IC2") (pin "112") (pinfunction "PTC0_112") (pintype "passive"))
    )
    (net (code "157") (name "unconnected-(IC2E-3V3-Pad122)") (class "Default")
      (node (ref "IC2") (pin "122") (pinfunction "3V3_122") (pintype "passive"))
    )
    (net (code "158") (name "unconnected-(IC2E-5V-Pad116)") (class "Default")
      (node (ref "IC2") (pin "116") (pinfunction "5V_116") (pintype "passive"))
    )
    (net (code "159") (name "unconnected-(IC2E-A0-Pad119)") (class "Default")
      (node (ref "IC2") (pin "119") (pinfunction "A0_119") (pintype "passive"))
    )
    (net (code "160") (name "unconnected-(IC2E-A1-Pad115)") (class "Default")
      (node (ref "IC2") (pin "115") (pinfunction "A1_115") (pintype "passive"))
    )
    (net (code "161") (name "unconnected-(IC2E-A2-Pad117)") (class "Default")
      (node (ref "IC2") (pin "117") (pinfunction "A2_117") (pintype "passive"))
    )
    (net (code "162") (name "unconnected-(IC2E-A3-Pad121)") (class "Default")
      (node (ref "IC2") (pin "121") (pinfunction "A3_121") (pintype "passive"))
    )
    (net (code "163") (name "unconnected-(IC2E-A4-Pad120)") (class "Default")
      (node (ref "IC2") (pin "120") (pinfunction "A4_120") (pintype "passive"))
    )
    (net (code "164") (name "unconnected-(IC2E-GND-Pad114)") (class "Default")
      (node (ref "IC2") (pin "114") (pinfunction "GND_114") (pintype "passive"))
    )
    (net (code "165") (name "unconnected-(IC2E-GND-Pad118)") (class "Default")
      (node (ref "IC2") (pin "118") (pinfunction "GND_118") (pintype "passive"))
    )
    (net (code "166") (name "unconnected-(IC2E-RES-Pad113)") (class "Default")
      (node (ref "IC2") (pin "113") (pinfunction "RES_113") (pintype "passive"))
    )
    (net (code "167") (name "unconnected-(P2-Pad1)") (class "Default")
      (node (ref "P2") (pin "1") (pinfunction "1_1") (pintype "passive"))
    )
    (net (code "168") (name "unconnected-(P2-Pad2)") (class "Default")
      (node (ref "P2") (pin "2") (pinfunction "2_2") (pintype "passive"))
    )
    (net (code "169") (name "unconnected-(P6-Pad1)") (class "Default")
      (node (ref "P6") (pin "1") (pinfunction "1_1") (pintype "passive"))
    )
    (net (code "170") (name "unconnected-(P6-Pad2)") (class "Default")
      (node (ref "P6") (pin "2") (pinfunction "2_2") (pintype "passive"))
    )
    (net (code "171") (name "unconnected-(P8-F3-Pad6)") (class "Default")
      (node (ref "P8") (pin "6") (pinfunction "F3_6") (pintype "passive"))
    )
    (net (code "172") (name "unconnected-(P8-FO-Pad14)") (class "Default")
      (node (ref "P8") (pin "14") (pinfunction "FO_14") (pintype "passive"))
    )
    (net (code "173") (name "unconnected-(P8-LE-Pad10)") (class "Default")
      (node (ref "P8") (pin "10") (pinfunction "LE_10") (pintype "passive"))
    )
    (net (code "174") (name "unconnected-(P8-OE-Pad4)") (class "Default")
      (node (ref "P8") (pin "4") (pinfunction "OE_4") (pintype "passive"))
    )
    (net (code "175") (name "unconnected-(P8-PW-Pad16)") (class "Default")
      (node (ref "P8") (pin "16") (pinfunction "PW_16") (pintype "passive"))
    )
    (net (code "176") (name "unconnected-(U1-~{RESET}-Pad8)") (class "Default")
      (node (ref "U1") (pin "8") (pinfunction "~{RESET}_8") (pintype "passive"))
    )
  )
)
